# GSRmeter.net
KiCad netlist of a schematic drawn in EAGLE
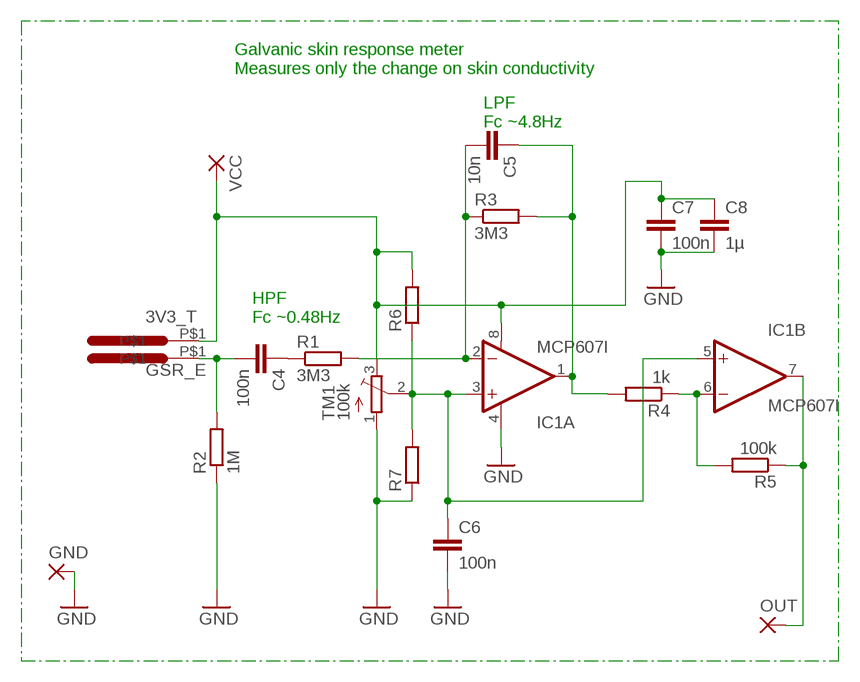
[diagram p0: schematic, sheet 1]

(export (version "E")
  (design (tool "Eeschema 10.0.6"))
  (components
    (comp (ref "C4")
      (value "100n")
      (footprint "eagle-import:C0603K")
      (libsource (lib "eagle-import") (part "C-EUC0603K"))
    )
    (comp (ref "C5")
      (value "10n")
      (footprint "eagle-import:C0603K")
      (libsource (lib "eagle-import") (part "C-EUC0603K"))
    )
    (comp (ref "C6")
      (value "100n")
      (footprint "eagle-import:C0603K")
      (libsource (lib "eagle-import") (part "C-EUC0603K"))
    )
    (comp (ref "C7")
      (value "100n")
      (footprint "eagle-import:C0603K")
      (libsource (lib "eagle-import") (part "C-EUC0603K"))
    )
    (comp (ref "C8")
      (value "1µ")
      (footprint "eagle-import:C0603K")
      (libsource (lib "eagle-import") (part "C-EUC0603K"))
    )
    (comp (ref "GND")
      (value "SMD5")
      (footprint "eagle-import:SMD2,54-5,08")
      (libsource (lib "eagle-import") (part "SMD5"))
    )
    (comp (ref "IC1")
      (value "MCP607I")
      (footprint "eagle-import:SO08")
      (libsource (lib "eagle-import") (part "OPAMP-DUALU"))
    )
    (comp (ref "OUT")
      (value "SMD5")
      (footprint "eagle-import:SMD2,54-5,08")
      (libsource (lib "eagle-import") (part "SMD5"))
    )
    (comp (ref "R1")
      (value "3M3")
      (footprint "eagle-import:R0603")
      (libsource (lib "eagle-import") (part "R-EU_R0603"))
    )
    (comp (ref "R2")
      (value "1M")
      (footprint "eagle-import:R0603")
      (libsource (lib "eagle-import") (part "R-EU_R0603"))
    )
    (comp (ref "R3")
      (value "3M3")
      (footprint "eagle-import:R0603")
      (libsource (lib "eagle-import") (part "R-EU_R0603"))
    )
    (comp (ref "R4")
      (value "1k")
      (footprint "eagle-import:R0603")
      (libsource (lib "eagle-import") (part "R-EU_R0603"))
    )
    (comp (ref "R5")
      (value "100k")
      (footprint "eagle-import:R0603")
      (libsource (lib "eagle-import") (part "R-EU_R0603"))
    )
    (comp (ref "R6")
      (value "R-EU_R0402")
      (footprint "eagle-import:R0402")
      (libsource (lib "eagle-import") (part "R-EU_R0402"))
    )
    (comp (ref "R7")
      (value "R-EU_R0402")
      (footprint "eagle-import:R0402")
      (libsource (lib "eagle-import") (part "R-EU_R0402"))
    )
    (comp (ref "TM1")
      (value "100k")
      (footprint "eagle-import:TC33X")
      (libsource (lib "eagle-import") (part "TRIMPOTTC33X"))
    )
    (comp (ref "U$1")
      (value "ELECTRODE")
      (footprint "eagle-import:ELECTRODE")
      (libsource (lib "eagle-import") (part "ELECTRODE"))
    )
    (comp (ref "U$2")
      (value "ELECTRODE")
      (footprint "eagle-import:ELECTRODE")
      (libsource (lib "eagle-import") (part "ELECTRODE"))
    )
    (comp (ref "VCC")
      (value "SMD5")
      (footprint "eagle-import:SMD2,54-5,08")
      (libsource (lib "eagle-import") (part "SMD5"))
    )
  )
  (nets
    (net (code "1") (name "/3V3_T") (class "Default")
      (node (ref "C7") (pin "1") (pinfunction "1_1") (pintype "passive"))
      (node (ref "C8") (pin "1") (pinfunction "1_1") (pintype "passive"))
      (node (ref "IC1") (pin "8") (pinfunction "V+_8") (pintype "power_in"))
      (node (ref "R6") (pin "2") (pinfunction "2_2") (pintype "passive"))
      (node (ref "TM1") (pin "3") (pinfunction "E_3") (pintype "passive"))
      (node (ref "U$1") (pin "P$1") (pinfunction "P$1_P$1") (pintype "bidirectional"))
      (node (ref "VCC") (pin "1") (pinfunction "P_1") (pintype "passive"))
    )
    (net (code "2") (name "/GSR_E") (class "Default")
      (node (ref "C4") (pin "2") (pinfunction "2_2") (pintype "passive"))
      (node (ref "R2") (pin "2") (pinfunction "2_2") (pintype "passive"))
      (node (ref "U$2") (pin "P$1") (pinfunction "P$1_P$1") (pintype "bidirectional"))
    )
    (net (code "3") (name "GND") (class "Default")
      (node (ref "C6") (pin "2") (pinfunction "2_2") (pintype "passive"))
      (node (ref "C7") (pin "2") (pinfunction "2_2") (pintype "passive"))
      (node (ref "C8") (pin "2") (pinfunction "2_2") (pintype "passive"))
      (node (ref "GND") (pin "1") (pinfunction "P_1") (pintype "passive"))
      (node (ref "IC1") (pin "4") (pinfunction "V-_4") (pintype "power_in"))
      (node (ref "R2") (pin "1") (pinfunction "1_1") (pintype "passive"))
      (node (ref "R7") (pin "1") (pinfunction "1_1") (pintype "passive"))
      (node (ref "TM1") (pin "1") (pinfunction "A_1") (pintype "passive"))
    )
    (net (code "4") (name "Net-(C4-Pad1)") (class "Default")
      (node (ref "C4") (pin "1") (pinfunction "1_1") (pintype "passive"))
      (node (ref "R1") (pin "1") (pinfunction "1_1") (pintype "passive"))
    )
    (net (code "5") (name "Net-(IC1A-+IN)") (class "Default")
      (node (ref "C6") (pin "1") (pinfunction "1_1") (pintype "passive"))
      (node (ref "IC1") (pin "3") (pinfunction "+IN_3") (pintype "input"))
      (node (ref "IC1") (pin "5") (pinfunction "+IN_5") (pintype "input"))
      (node (ref "R6") (pin "1") (pinfunction "1_1") (pintype "passive"))
      (node (ref "R7") (pin "2") (pinfunction "2_2") (pintype "passive"))
      (node (ref "TM1") (pin "2") (pinfunction "S_2") (pintype "passive"))
    )
    (net (code "6") (name "Net-(IC1A--IN)") (class "Default")
      (node (ref "C5") (pin "2") (pinfunction "2_2") (pintype "passive"))
      (node (ref "IC1") (pin "2") (pinfunction "-IN_2") (pintype "input"))
      (node (ref "R1") (pin "2") (pinfunction "2_2") (pintype "passive"))
      (node (ref "R3") (pin "1") (pinfunction "1_1") (pintype "passive"))
    )
    (net (code "7") (name "Net-(IC1A-OUT)") (class "Default")
      (node (ref "C5") (pin "1") (pinfunction "1_1") (pintype "passive"))
      (node (ref "IC1") (pin "1") (pinfunction "OUT_1") (pintype "output"))
      (node (ref "R3") (pin "2") (pinfunction "2_2") (pintype "passive"))
      (node (ref "R4") (pin "2") (pinfunction "2_2") (pintype "passive"))
    )
    (net (code "8") (name "Net-(IC1B--IN)") (class "Default")
      (node (ref "IC1") (pin "6") (pinfunction "-IN_6") (pintype "input"))
      (node (ref "R4") (pin "1") (pinfunction "1_1") (pintype "passive"))
      (node (ref "R5") (pin "2") (pinfunction "2_2") (pintype "passive"))
    )
    (net (code "9") (name "Net-(IC1B-OUT)") (class "Default")
      (node (ref "IC1") (pin "7") (pinfunction "OUT_7") (pintype "output"))
      (node (ref "OUT") (pin "1") (pinfunction "P_1") (pintype "passive"))
      (node (ref "R5") (pin "1") (pinfunction "1_1") (pintype "passive"))
    )
  )
)
